# WS2812_hart.net
KiCad netlist of a schematic drawn in EAGLE
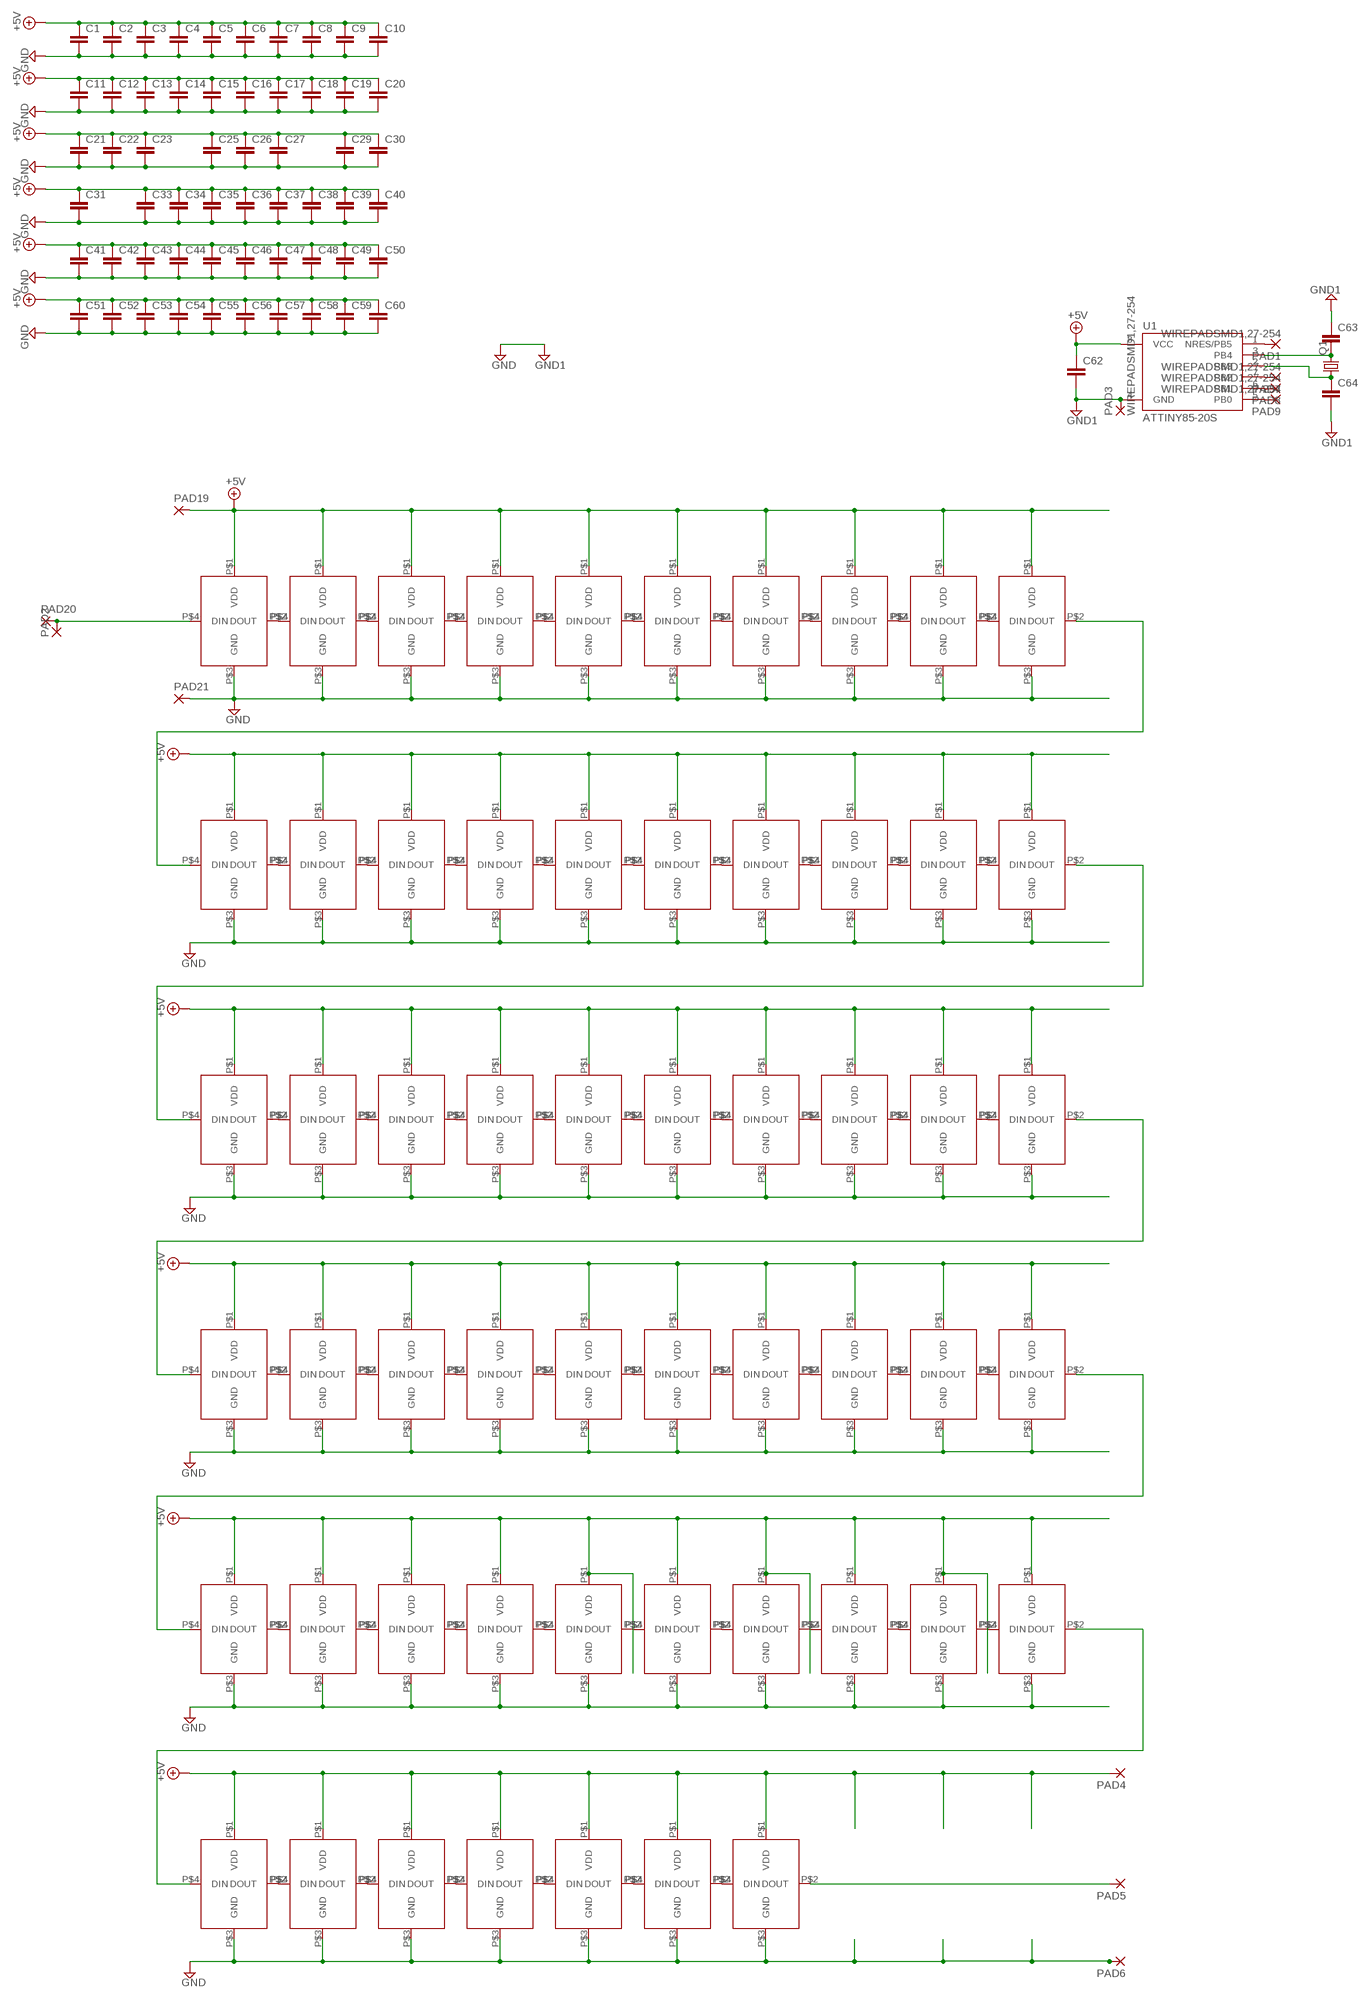
[diagram p0: schematic, sheet 1]

(export (version "E")
  (design (tool "Eeschema 10.0.6"))
  (components
    (comp (ref "C1")
      (value "C-EUC1206K")
      (footprint "eagle-import:C1206K")
      (libsource (lib "eagle-import") (part "C-EUC1206K"))
    )
    (comp (ref "C2")
      (value "C-EUC1206K")
      (footprint "eagle-import:C1206K")
      (libsource (lib "eagle-import") (part "C-EUC1206K"))
    )
    (comp (ref "C3")
      (value "C-EUC1206K")
      (footprint "eagle-import:C1206K")
      (libsource (lib "eagle-import") (part "C-EUC1206K"))
    )
    (comp (ref "C4")
      (value "C-EUC1206K")
      (footprint "eagle-import:C1206K")
      (libsource (lib "eagle-import") (part "C-EUC1206K"))
    )
    (comp (ref "C5")
      (value "C-EUC1206K")
      (footprint "eagle-import:C1206K")
      (libsource (lib "eagle-import") (part "C-EUC1206K"))
    )
    (comp (ref "C6")
      (value "C-EUC1206K")
      (footprint "eagle-import:C1206K")
      (libsource (lib "eagle-import") (part "C-EUC1206K"))
    )
    (comp (ref "C7")
      (value "C-EUC1206K")
      (footprint "eagle-import:C1206K")
      (libsource (lib "eagle-import") (part "C-EUC1206K"))
    )
    (comp (ref "C8")
      (value "C-EUC1206K")
      (footprint "eagle-import:C1206K")
      (libsource (lib "eagle-import") (part "C-EUC1206K"))
    )
    (comp (ref "C9")
      (value "C-EUC1206K")
      (footprint "eagle-import:C1206K")
      (libsource (lib "eagle-import") (part "C-EUC1206K"))
    )
    (comp (ref "C10")
      (value "C-EUC1206K")
      (footprint "eagle-import:C1206K")
      (libsource (lib "eagle-import") (part "C-EUC1206K"))
    )
    (comp (ref "C11")
      (value "C-EUC1206K")
      (footprint "eagle-import:C1206K")
      (libsource (lib "eagle-import") (part "C-EUC1206K"))
    )
    (comp (ref "C12")
      (value "C-EUC1206K")
      (footprint "eagle-import:C1206K")
      (libsource (lib "eagle-import") (part "C-EUC1206K"))
    )
    (comp (ref "C13")
      (value "C-EUC1206K")
      (footprint "eagle-import:C1206K")
      (libsource (lib "eagle-import") (part "C-EUC1206K"))
    )
    (comp (ref "C14")
      (value "C-EUC1206K")
      (footprint "eagle-import:C1206K")
      (libsource (lib "eagle-import") (part "C-EUC1206K"))
    )
    (comp (ref "C15")
      (value "C-EUC1206K")
      (footprint "eagle-import:C1206K")
      (libsource (lib "eagle-import") (part "C-EUC1206K"))
    )
    (comp (ref "C16")
      (value "C-EUC1206K")
      (footprint "eagle-import:C1206K")
      (libsource (lib "eagle-import") (part "C-EUC1206K"))
    )
    (comp (ref "C17")
      (value "C-EUC0805K")
      (footprint "eagle-import:C0805K")
      (libsource (lib "eagle-import") (part "C-EUC0805K"))
    )
    (comp (ref "C18")
      (value "C-EUC1206K")
      (footprint "eagle-import:C1206K")
      (libsource (lib "eagle-import") (part "C-EUC1206K"))
    )
    (comp (ref "C19")
      (value "C-EUC1206K")
      (footprint "eagle-import:C1206K")
      (libsource (lib "eagle-import") (part "C-EUC1206K"))
    )
    (comp (ref "C20")
      (value "C-EUC1206K")
      (footprint "eagle-import:C1206K")
      (libsource (lib "eagle-import") (part "C-EUC1206K"))
    )
    (comp (ref "C21")
      (value "C-EUC1206K")
      (footprint "eagle-import:C1206K")
      (libsource (lib "eagle-import") (part "C-EUC1206K"))
    )
    (comp (ref "C22")
      (value "C-EUC1206K")
      (footprint "eagle-import:C1206K")
      (libsource (lib "eagle-import") (part "C-EUC1206K"))
    )
    (comp (ref "C23")
      (value "C-EUC1206K")
      (footprint "eagle-import:C1206K")
      (libsource (lib "eagle-import") (part "C-EUC1206K"))
    )
    (comp (ref "C25")
      (value "C-EUC1206K")
      (footprint "eagle-import:C1206K")
      (libsource (lib "eagle-import") (part "C-EUC1206K"))
    )
    (comp (ref "C26")
      (value "C-EUC1206K")
      (footprint "eagle-import:C1206K")
      (libsource (lib "eagle-import") (part "C-EUC1206K"))
    )
    (comp (ref "C27")
      (value "C-EUC1206K")
      (footprint "eagle-import:C1206K")
      (libsource (lib "eagle-import") (part "C-EUC1206K"))
    )
    (comp (ref "C29")
      (value "C-EUC1206K")
      (footprint "eagle-import:C1206K")
      (libsource (lib "eagle-import") (part "C-EUC1206K"))
    )
    (comp (ref "C30")
      (value "C-EUC1206K")
      (footprint "eagle-import:C1206K")
      (libsource (lib "eagle-import") (part "C-EUC1206K"))
    )
    (comp (ref "C31")
      (value "C-EUC1206K")
      (footprint "eagle-import:C1206K")
      (libsource (lib "eagle-import") (part "C-EUC1206K"))
    )
    (comp (ref "C33")
      (value "C-EUC1206K")
      (footprint "eagle-import:C1206K")
      (libsource (lib "eagle-import") (part "C-EUC1206K"))
    )
    (comp (ref "C34")
      (value "C-EUC1206K")
      (footprint "eagle-import:C1206K")
      (libsource (lib "eagle-import") (part "C-EUC1206K"))
    )
    (comp (ref "C35")
      (value "C-EUC1206K")
      (footprint "eagle-import:C1206K")
      (libsource (lib "eagle-import") (part "C-EUC1206K"))
    )
    (comp (ref "C36")
      (value "C-EUC1206K")
      (footprint "eagle-import:C1206K")
      (libsource (lib "eagle-import") (part "C-EUC1206K"))
    )
    (comp (ref "C37")
      (value "C-EUC1206K")
      (footprint "eagle-import:C1206K")
      (libsource (lib "eagle-import") (part "C-EUC1206K"))
    )
    (comp (ref "C38")
      (value "C-EUC1206K")
      (footprint "eagle-import:C1206K")
      (libsource (lib "eagle-import") (part "C-EUC1206K"))
    )
    (comp (ref "C39")
      (value "C-EUC1206K")
      (footprint "eagle-import:C1206K")
      (libsource (lib "eagle-import") (part "C-EUC1206K"))
    )
    (comp (ref "C40")
      (value "C-EUC1206K")
      (footprint "eagle-import:C1206K")
      (libsource (lib "eagle-import") (part "C-EUC1206K"))
    )
    (comp (ref "C41")
      (value "C-EUC1206K")
      (footprint "eagle-import:C1206K")
      (libsource (lib "eagle-import") (part "C-EUC1206K"))
    )
    (comp (ref "C42")
      (value "C-EUC1206K")
      (footprint "eagle-import:C1206K")
      (libsource (lib "eagle-import") (part "C-EUC1206K"))
    )
    (comp (ref "C43")
      (value "C-EUC1206K")
      (footprint "eagle-import:C1206K")
      (libsource (lib "eagle-import") (part "C-EUC1206K"))
    )
    (comp (ref "C44")
      (value "C-EUC1206K")
      (footprint "eagle-import:C1206K")
      (libsource (lib "eagle-import") (part "C-EUC1206K"))
    )
    (comp (ref "C45")
      (value "C-EUC1206K")
      (footprint "eagle-import:C1206K")
      (libsource (lib "eagle-import") (part "C-EUC1206K"))
    )
    (comp (ref "C46")
      (value "C-EUC1206K")
      (footprint "eagle-import:C1206K")
      (libsource (lib "eagle-import") (part "C-EUC1206K"))
    )
    (comp (ref "C47")
      (value "C-EUC1206K")
      (footprint "eagle-import:C1206K")
      (libsource (lib "eagle-import") (part "C-EUC1206K"))
    )
    (comp (ref "C48")
      (value "C-EUC1206K")
      (footprint "eagle-import:C1206K")
      (libsource (lib "eagle-import") (part "C-EUC1206K"))
    )
    (comp (ref "C49")
      (value "C-EUC1206K")
      (footprint "eagle-import:C1206K")
      (libsource (lib "eagle-import") (part "C-EUC1206K"))
    )
    (comp (ref "C50")
      (value "C-EUC1206K")
      (footprint "eagle-import:C1206K")
      (libsource (lib "eagle-import") (part "C-EUC1206K"))
    )
    (comp (ref "C51")
      (value "C-EUC1206K")
      (footprint "eagle-import:C1206K")
      (libsource (lib "eagle-import") (part "C-EUC1206K"))
    )
    (comp (ref "C52")
      (value "C-EUC0805K")
      (footprint "eagle-import:C0805K")
      (libsource (lib "eagle-import") (part "C-EUC0805K"))
    )
    (comp (ref "C53")
      (value "C-EUC1206K")
      (footprint "eagle-import:C1206K")
      (libsource (lib "eagle-import") (part "C-EUC1206K"))
    )
    (comp (ref "C54")
      (value "C-EUC1206K")
      (footprint "eagle-import:C1206K")
      (libsource (lib "eagle-import") (part "C-EUC1206K"))
    )
    (comp (ref "C55")
      (value "C-EUC1206K")
      (footprint "eagle-import:C1206K")
      (libsource (lib "eagle-import") (part "C-EUC1206K"))
    )
    (comp (ref "C56")
      (value "C-EUC1206K")
      (footprint "eagle-import:C1206K")
      (libsource (lib "eagle-import") (part "C-EUC1206K"))
    )
    (comp (ref "C57")
      (value "C-EUC1206K")
      (footprint "eagle-import:C1206K")
      (libsource (lib "eagle-import") (part "C-EUC1206K"))
    )
    (comp (ref "C58")
      (value "C-EUC1206K")
      (footprint "eagle-import:C1206K")
      (libsource (lib "eagle-import") (part "C-EUC1206K"))
    )
    (comp (ref "C59")
      (value "C-EUC1206K")
      (footprint "eagle-import:C1206K")
      (libsource (lib "eagle-import") (part "C-EUC1206K"))
    )
    (comp (ref "C60")
      (value "C-EUC1206K")
      (footprint "eagle-import:C1206K")
      (libsource (lib "eagle-import") (part "C-EUC1206K"))
    )
    (comp (ref "C62")
      (value "C-EUC0805K")
      (footprint "eagle-import:C0805K")
      (libsource (lib "eagle-import") (part "C-EUC0805K"))
    )
    (comp (ref "C63")
      (value "C-EUC0603K")
      (footprint "eagle-import:C0603K")
      (libsource (lib "eagle-import") (part "C-EUC0603K"))
    )
    (comp (ref "C64")
      (value "C-EUC0603K")
      (footprint "eagle-import:C0603K")
      (libsource (lib "eagle-import") (part "C-EUC0603K"))
    )
    (comp (ref "PAD1")
      (value "WIREPADSMD1,27-254")
      (footprint "eagle-import:SMD1,27-2,54")
      (libsource (lib "eagle-import") (part "WIREPADSMD1,27-254"))
    )
    (comp (ref "PAD2")
      (value "SMD5")
      (footprint "eagle-import:SMD2,54-5,08")
      (libsource (lib "eagle-import") (part "SMD5"))
    )
    (comp (ref "PAD3")
      (value "WIREPADSMD1,27-254")
      (footprint "eagle-import:SMD1,27-2,54")
      (libsource (lib "eagle-import") (part "WIREPADSMD1,27-254"))
    )
    (comp (ref "PAD4")
      (value "1,6/0,8")
      (footprint "eagle-import:1,6_0,8")
      (libsource (lib "eagle-import") (part "1,6/0,8"))
    )
    (comp (ref "PAD5")
      (value "1,6/0,8")
      (footprint "eagle-import:1,6_0,8")
      (libsource (lib "eagle-import") (part "1,6/0,8"))
    )
    (comp (ref "PAD6")
      (value "1,6/0,8")
      (footprint "eagle-import:1,6_0,8")
      (libsource (lib "eagle-import") (part "1,6/0,8"))
    )
    (comp (ref "PAD7")
      (value "WIREPADSMD1,27-254")
      (footprint "eagle-import:SMD1,27-2,54")
      (libsource (lib "eagle-import") (part "WIREPADSMD1,27-254"))
    )
    (comp (ref "PAD8")
      (value "WIREPADSMD1,27-254")
      (footprint "eagle-import:SMD1,27-2,54")
      (libsource (lib "eagle-import") (part "WIREPADSMD1,27-254"))
    )
    (comp (ref "PAD9")
      (value "WIREPADSMD1,27-254")
      (footprint "eagle-import:SMD1,27-2,54")
      (libsource (lib "eagle-import") (part "WIREPADSMD1,27-254"))
    )
    (comp (ref "PAD19")
      (value "1,6/0,8")
      (footprint "eagle-import:1,6_0,8")
      (libsource (lib "eagle-import") (part "1,6/0,8"))
    )
    (comp (ref "PAD20")
      (value "1,6/0,8")
      (footprint "eagle-import:1,6_0,8")
      (libsource (lib "eagle-import") (part "1,6/0,8"))
    )
    (comp (ref "PAD21")
      (value "1,6/0,8")
      (footprint "eagle-import:1,6_0,8")
      (libsource (lib "eagle-import") (part "1,6/0,8"))
    )
    (comp (ref "Q1")
      (value "CRYSTALHC49S")
      (footprint "eagle-import:HC49_S")
      (libsource (lib "eagle-import") (part "CRYSTALHC49S"))
    )
    (comp (ref "U$1")
      (value "WS2812B")
      (footprint "eagle-import:PLCC-4")
      (libsource (lib "eagle-import") (part "WS2812B"))
    )
    (comp (ref "U$2")
      (value "WS2812B")
      (footprint "eagle-import:PLCC-4")
      (libsource (lib "eagle-import") (part "WS2812B"))
    )
    (comp (ref "U$3")
      (value "WS2812B")
      (footprint "eagle-import:PLCC-4")
      (libsource (lib "eagle-import") (part "WS2812B"))
    )
    (comp (ref "U$4")
      (value "WS2812B")
      (footprint "eagle-import:PLCC-4")
      (libsource (lib "eagle-import") (part "WS2812B"))
    )
    (comp (ref "U$5")
      (value "WS2812B")
      (footprint "eagle-import:PLCC-4")
      (libsource (lib "eagle-import") (part "WS2812B"))
    )
    (comp (ref "U$6")
      (value "WS2812B")
      (footprint "eagle-import:PLCC-4")
      (libsource (lib "eagle-import") (part "WS2812B"))
    )
    (comp (ref "U$7")
      (value "WS2812B")
      (footprint "eagle-import:PLCC-4")
      (libsource (lib "eagle-import") (part "WS2812B"))
    )
    (comp (ref "U$8")
      (value "WS2812B")
      (footprint "eagle-import:PLCC-4")
      (libsource (lib "eagle-import") (part "WS2812B"))
    )
    (comp (ref "U$9")
      (value "WS2812B")
      (footprint "eagle-import:PLCC-4")
      (libsource (lib "eagle-import") (part "WS2812B"))
    )
    (comp (ref "U$10")
      (value "WS2812B")
      (footprint "eagle-import:PLCC-4")
      (libsource (lib "eagle-import") (part "WS2812B"))
    )
    (comp (ref "U$11")
      (value "WS2812B")
      (footprint "eagle-import:PLCC-4")
      (libsource (lib "eagle-import") (part "WS2812B"))
    )
    (comp (ref "U$12")
      (value "WS2812B")
      (footprint "eagle-import:PLCC-4")
      (libsource (lib "eagle-import") (part "WS2812B"))
    )
    (comp (ref "U$13")
      (value "WS2812B")
      (footprint "eagle-import:PLCC-4")
      (libsource (lib "eagle-import") (part "WS2812B"))
    )
    (comp (ref "U$14")
      (value "WS2812B")
      (footprint "eagle-import:PLCC-4")
      (libsource (lib "eagle-import") (part "WS2812B"))
    )
    (comp (ref "U$15")
      (value "WS2812B")
      (footprint "eagle-import:PLCC-4")
      (libsource (lib "eagle-import") (part "WS2812B"))
    )
    (comp (ref "U$16")
      (value "WS2812B")
      (footprint "eagle-import:PLCC-4")
      (libsource (lib "eagle-import") (part "WS2812B"))
    )
    (comp (ref "U$17")
      (value "WS2812B")
      (footprint "eagle-import:PLCC-4")
      (libsource (lib "eagle-import") (part "WS2812B"))
    )
    (comp (ref "U$18")
      (value "WS2812B")
      (footprint "eagle-import:PLCC-4")
      (libsource (lib "eagle-import") (part "WS2812B"))
    )
    (comp (ref "U$19")
      (value "WS2812B")
      (footprint "eagle-import:PLCC-4")
      (libsource (lib "eagle-import") (part "WS2812B"))
    )
    (comp (ref "U$20")
      (value "WS2812B")
      (footprint "eagle-import:PLCC-4")
      (libsource (lib "eagle-import") (part "WS2812B"))
    )
    (comp (ref "U$21")
      (value "WS2812B")
      (footprint "eagle-import:PLCC-4")
      (libsource (lib "eagle-import") (part "WS2812B"))
    )
    (comp (ref "U$22")
      (value "WS2812B")
      (footprint "eagle-import:PLCC-4")
      (libsource (lib "eagle-import") (part "WS2812B"))
    )
    (comp (ref "U$23")
      (value "WS2812B")
      (footprint "eagle-import:PLCC-4")
      (libsource (lib "eagle-import") (part "WS2812B"))
    )
    (comp (ref "U$24")
      (value "WS2812B")
      (footprint "eagle-import:PLCC-4")
      (libsource (lib "eagle-import") (part "WS2812B"))
    )
    (comp (ref "U$25")
      (value "WS2812B")
      (footprint "eagle-import:PLCC-4")
      (libsource (lib "eagle-import") (part "WS2812B"))
    )
    (comp (ref "U$26")
      (value "WS2812B")
      (footprint "eagle-import:PLCC-4")
      (libsource (lib "eagle-import") (part "WS2812B"))
    )
    (comp (ref "U$27")
      (value "WS2812B")
      (footprint "eagle-import:PLCC-4")
      (libsource (lib "eagle-import") (part "WS2812B"))
    )
    (comp (ref "U$28")
      (value "WS2812B")
      (footprint "eagle-import:PLCC-4")
      (libsource (lib "eagle-import") (part "WS2812B"))
    )
    (comp (ref "U$29")
      (value "WS2812B")
      (footprint "eagle-import:PLCC-4")
      (libsource (lib "eagle-import") (part "WS2812B"))
    )
    (comp (ref "U$30")
      (value "WS2812B")
      (footprint "eagle-import:PLCC-4")
      (libsource (lib "eagle-import") (part "WS2812B"))
    )
    (comp (ref "U$31")
      (value "WS2812B")
      (footprint "eagle-import:PLCC-4")
      (libsource (lib "eagle-import") (part "WS2812B"))
    )
    (comp (ref "U$32")
      (value "WS2812B")
      (footprint "eagle-import:PLCC-4")
      (libsource (lib "eagle-import") (part "WS2812B"))
    )
    (comp (ref "U$33")
      (value "WS2812B")
      (footprint "eagle-import:PLCC-4")
      (libsource (lib "eagle-import") (part "WS2812B"))
    )
    (comp (ref "U$34")
      (value "WS2812B")
      (footprint "eagle-import:PLCC-4")
      (libsource (lib "eagle-import") (part "WS2812B"))
    )
    (comp (ref "U$35")
      (value "WS2812B")
      (footprint "eagle-import:PLCC-4")
      (libsource (lib "eagle-import") (part "WS2812B"))
    )
    (comp (ref "U$36")
      (value "WS2812B")
      (footprint "eagle-import:PLCC-4")
      (libsource (lib "eagle-import") (part "WS2812B"))
    )
    (comp (ref "U$37")
      (value "WS2812B")
      (footprint "eagle-import:PLCC-4")
      (libsource (lib "eagle-import") (part "WS2812B"))
    )
    (comp (ref "U$38")
      (value "WS2812B")
      (footprint "eagle-import:PLCC-4")
      (libsource (lib "eagle-import") (part "WS2812B"))
    )
    (comp (ref "U$39")
      (value "WS2812B")
      (footprint "eagle-import:PLCC-4")
      (libsource (lib "eagle-import") (part "WS2812B"))
    )
    (comp (ref "U$40")
      (value "WS2812B")
      (footprint "eagle-import:PLCC-4")
      (libsource (lib "eagle-import") (part "WS2812B"))
    )
    (comp (ref "U$41")
      (value "WS2812B")
      (footprint "eagle-import:PLCC-4")
      (libsource (lib "eagle-import") (part "WS2812B"))
    )
    (comp (ref "U$42")
      (value "WS2812B")
      (footprint "eagle-import:PLCC-4")
      (libsource (lib "eagle-import") (part "WS2812B"))
    )
    (comp (ref "U$43")
      (value "WS2812B")
      (footprint "eagle-import:PLCC-4")
      (libsource (lib "eagle-import") (part "WS2812B"))
    )
    (comp (ref "U$44")
      (value "WS2812B")
      (footprint "eagle-import:PLCC-4")
      (libsource (lib "eagle-import") (part "WS2812B"))
    )
    (comp (ref "U$45")
      (value "WS2812B")
      (footprint "eagle-import:PLCC-4")
      (libsource (lib "eagle-import") (part "WS2812B"))
    )
    (comp (ref "U$46")
      (value "WS2812B")
      (footprint "eagle-import:PLCC-4")
      (libsource (lib "eagle-import") (part "WS2812B"))
    )
    (comp (ref "U$47")
      (value "WS2812B")
      (footprint "eagle-import:PLCC-4")
      (libsource (lib "eagle-import") (part "WS2812B"))
    )
    (comp (ref "U$48")
      (value "WS2812B")
      (footprint "eagle-import:PLCC-4")
      (libsource (lib "eagle-import") (part "WS2812B"))
    )
    (comp (ref "U$49")
      (value "WS2812B")
      (footprint "eagle-import:PLCC-4")
      (libsource (lib "eagle-import") (part "WS2812B"))
    )
    (comp (ref "U$50")
      (value "WS2812B")
      (footprint "eagle-import:PLCC-4")
      (libsource (lib "eagle-import") (part "WS2812B"))
    )
    (comp (ref "U$51")
      (value "WS2812B")
      (footprint "eagle-import:PLCC-4")
      (libsource (lib "eagle-import") (part "WS2812B"))
    )
    (comp (ref "U$52")
      (value "WS2812B")
      (footprint "eagle-import:PLCC-4")
      (libsource (lib "eagle-import") (part "WS2812B"))
    )
    (comp (ref "U$53")
      (value "WS2812B")
      (footprint "eagle-import:PLCC-4")
      (libsource (lib "eagle-import") (part "WS2812B"))
    )
    (comp (ref "U$54")
      (value "WS2812B")
      (footprint "eagle-import:PLCC-4")
      (libsource (lib "eagle-import") (part "WS2812B"))
    )
    (comp (ref "U$55")
      (value "WS2812B")
      (footprint "eagle-import:PLCC-4")
      (libsource (lib "eagle-import") (part "WS2812B"))
    )
    (comp (ref "U$56")
      (value "WS2812B")
      (footprint "eagle-import:PLCC-4")
      (libsource (lib "eagle-import") (part "WS2812B"))
    )
    (comp (ref "U$57")
      (value "WS2812B")
      (footprint "eagle-import:PLCC-4")
      (libsource (lib "eagle-import") (part "WS2812B"))
    )
    (comp (ref "U1")
      (value "ATTINY85-20S")
      (footprint "eagle-import:SOIC8_EIAJ_208MIL")
      (libsource (lib "eagle-import") (part "ATTINY85S-20"))
    )
  )
  (nets
    (net (code "1") (name "+5V") (class "Default")
      (node (ref "C1") (pin "1") (pinfunction "1_1") (pintype "passive"))
      (node (ref "C10") (pin "1") (pinfunction "1_1") (pintype "passive"))
      (node (ref "C11") (pin "1") (pinfunction "1_1") (pintype "passive"))
      (node (ref "C12") (pin "1") (pinfunction "1_1") (pintype "passive"))
      (node (ref "C13") (pin "1") (pinfunction "1_1") (pintype "passive"))
      (node (ref "C14") (pin "1") (pinfunction "1_1") (pintype "passive"))
      (node (ref "C15") (pin "1") (pinfunction "1_1") (pintype "passive"))
      (node (ref "C16") (pin "1") (pinfunction "1_1") (pintype "passive"))
      (node (ref "C17") (pin "1") (pinfunction "1_1") (pintype "passive"))
      (node (ref "C18") (pin "1") (pinfunction "1_1") (pintype "passive"))
      (node (ref "C19") (pin "1") (pinfunction "1_1") (pintype "passive"))
      (node (ref "C2") (pin "1") (pinfunction "1_1") (pintype "passive"))
      (node (ref "C20") (pin "1") (pinfunction "1_1") (pintype "passive"))
      (node (ref "C21") (pin "1") (pinfunction "1_1") (pintype "passive"))
      (node (ref "C22") (pin "1") (pinfunction "1_1") (pintype "passive"))
      (node (ref "C23") (pin "1") (pinfunction "1_1") (pintype "passive"))
      (node (ref "C25") (pin "1") (pinfunction "1_1") (pintype "passive"))
      (node (ref "C26") (pin "1") (pinfunction "1_1") (pintype "passive"))
      (node (ref "C27") (pin "1") (pinfunction "1_1") (pintype "passive"))
      (node (ref "C29") (pin "1") (pinfunction "1_1") (pintype "passive"))
      (node (ref "C3") (pin "1") (pinfunction "1_1") (pintype "passive"))
      (node (ref "C30") (pin "1") (pinfunction "1_1") (pintype "passive"))
      (node (ref "C31") (pin "1") (pinfunction "1_1") (pintype "passive"))
      (node (ref "C33") (pin "1") (pinfunction "1_1") (pintype "passive"))
      (node (ref "C34") (pin "1") (pinfunction "1_1") (pintype "passive"))
      (node (ref "C35") (pin "1") (pinfunction "1_1") (pintype "passive"))
      (node (ref "C36") (pin "1") (pinfunction "1_1") (pintype "passive"))
      (node (ref "C37") (pin "1") (pinfunction "1_1") (pintype "passive"))
      (node (ref "C38") (pin "1") (pinfunction "1_1") (pintype "passive"))
      (node (ref "C39") (pin "1") (pinfunction "1_1") (pintype "passive"))
      (node (ref "C4") (pin "1") (pinfunction "1_1") (pintype "passive"))
      (node (ref "C40") (pin "1") (pinfunction "1_1") (pintype "passive"))
      (node (ref "C41") (pin "1") (pinfunction "1_1") (pintype "passive"))
      (node (ref "C42") (pin "1") (pinfunction "1_1") (pintype "passive"))
      (node (ref "C43") (pin "1") (pinfunction "1_1") (pintype "passive"))
      (node (ref "C44") (pin "1") (pinfunction "1_1") (pintype "passive"))
      (node (ref "C45") (pin "1") (pinfunction "1_1") (pintype "passive"))
      (node (ref "C46") (pin "1") (pinfunction "1_1") (pintype "passive"))
      (node (ref "C47") (pin "1") (pinfunction "1_1") (pintype "passive"))
      (node (ref "C48") (pin "1") (pinfunction "1_1") (pintype "passive"))
      (node (ref "C49") (pin "1") (pinfunction "1_1") (pintype "passive"))
      (node (ref "C5") (pin "1") (pinfunction "1_1") (pintype "passive"))
      (node (ref "C50") (pin "1") (pinfunction "1_1") (pintype "passive"))
      (node (ref "C51") (pin "1") (pinfunction "1_1") (pintype "passive"))
      (node (ref "C52") (pin "1") (pinfunction "1_1") (pintype "passive"))
      (node (ref "C53") (pin "1") (pinfunction "1_1") (pintype "passive"))
      (node (ref "C54") (pin "1") (pinfunction "1_1") (pintype "passive"))
      (node (ref "C55") (pin "1") (pinfunction "1_1") (pintype "passive"))
      (node (ref "C56") (pin "1") (pinfunction "1_1") (pintype "passive"))
      (node (ref "C57") (pin "1") (pinfunction "1_1") (pintype "passive"))
      (node (ref "C58") (pin "1") (pinfunction "1_1") (pintype "passive"))
      (node (ref "C59") (pin "1") (pinfunction "1_1") (pintype "passive"))
      (node (ref "C6") (pin "1") (pinfunction "1_1") (pintype "passive"))
      (node (ref "C60") (pin "1") (pinfunction "1_1") (pintype "passive"))
      (node (ref "C62") (pin "1") (pinfunction "1_1") (pintype "passive"))
      (node (ref "C7") (pin "1") (pinfunction "1_1") (pintype "passive"))
      (node (ref "C8") (pin "1") (pinfunction "1_1") (pintype "passive"))
      (node (ref "C9") (pin "1") (pinfunction "1_1") (pintype "passive"))
      (node (ref "PAD19") (pin "1") (pinfunction "P_1") (pintype "passive"))
      (node (ref "PAD4") (pin "1") (pinfunction "P_1") (pintype "passive"))
      (node (ref "U$1") (pin "P$1") (pinfunction "VDD_P$1") (pintype "power_in"))
      (node (ref "U$10") (pin "P$1") (pinfunction "VDD_P$1") (pintype "power_in"))
      (node (ref "U$11") (pin "P$1") (pinfunction "VDD_P$1") (pintype "power_in"))
      (node (ref "U$12") (pin "P$1") (pinfunction "VDD_P$1") (pintype "power_in"))
      (node (ref "U$13") (pin "P$1") (pinfunction "VDD_P$1") (pintype "power_in"))
      (node (ref "U$14") (pin "P$1") (pinfunction "VDD_P$1") (pintype "power_in"))
      (node (ref "U$15") (pin "P$1") (pinfunction "VDD_P$1") (pintype "power_in"))
      (node (ref "U$16") (pin "P$1") (pinfunction "VDD_P$1") (pintype "power_in"))
      (node (ref "U$17") (pin "P$1") (pinfunction "VDD_P$1") (pintype "power_in"))
      (node (ref "U$18") (pin "P$1") (pinfunction "VDD_P$1") (pintype "power_in"))
      (node (ref "U$19") (pin "P$1") (pinfunction "VDD_P$1") (pintype "power_in"))
      (node (ref "U$2") (pin "P$1") (pinfunction "VDD_P$1") (pintype "power_in"))
      (node (ref "U$20") (pin "P$1") (pinfunction "VDD_P$1") (pintype "power_in"))
      (node (ref "U$21") (pin "P$1") (pinfunction "VDD_P$1") (pintype "power_in"))
      (node (ref "U$22") (pin "P$1") (pinfunction "VDD_P$1") (pintype "power_in"))
      (node (ref "U$23") (pin "P$1") (pinfunction "VDD_P$1") (pintype "power_in"))
      (node (ref "U$24") (pin "P$1") (pinfunction "VDD_P$1") (pintype "power_in"))
      (node (ref "U$25") (pin "P$1") (pinfunction "VDD_P$1") (pintype "power_in"))
      (node (ref "U$26") (pin "P$1") (pinfunction "VDD_P$1") (pintype "power_in"))
      (node (ref "U$27") (pin "P$1") (pinfunction "VDD_P$1") (pintype "power_in"))
      (node (ref "U$28") (pin "P$1") (pinfunction "VDD_P$1") (pintype "power_in"))
      (node (ref "U$29") (pin "P$1") (pinfunction "VDD_P$1") (pintype "power_in"))
      (node (ref "U$3") (pin "P$1") (pinfunction "VDD_P$1") (pintype "power_in"))
      (node (ref "U$30") (pin "P$1") (pinfunction "VDD_P$1") (pintype "power_in"))
      (node (ref "U$31") (pin "P$1") (pinfunction "VDD_P$1") (pintype "power_in"))
      (node (ref "U$32") (pin "P$1") (pinfunction "VDD_P$1") (pintype "power_in"))
      (node (ref "U$33") (pin "P$1") (pinfunction "VDD_P$1") (pintype "power_in"))
      (node (ref "U$34") (pin "P$1") (pinfunction "VDD_P$1") (pintype "power_in"))
      (node (ref "U$35") (pin "P$1") (pinfunction "VDD_P$1") (pintype "power_in"))
      (node (ref "U$36") (pin "P$1") (pinfunction "VDD_P$1") (pintype "power_in"))
      (node (ref "U$37") (pin "P$1") (pinfunction "VDD_P$1") (pintype "power_in"))
      (node (ref "U$38") (pin "P$1") (pinfunction "VDD_P$1") (pintype "power_in"))
      (node (ref "U$39") (pin "P$1") (pinfunction "VDD_P$1") (pintype "power_in"))
      (node (ref "U$4") (pin "P$1") (pinfunction "VDD_P$1") (pintype "power_in"))
      (node (ref "U$40") (pin "P$1") (pinfunction "VDD_P$1") (pintype "power_in"))
      (node (ref "U$41") (pin "P$1") (pinfunction "VDD_P$1") (pintype "power_in"))
      (node (ref "U$42") (pin "P$1") (pinfunction "VDD_P$1") (pintype "power_in"))
      (node (ref "U$43") (pin "P$1") (pinfunction "VDD_P$1") (pintype "power_in"))
      (node (ref "U$44") (pin "P$1") (pinfunction "VDD_P$1") (pintype "power_in"))
      (node (ref "U$45") (pin "P$1") (pinfunction "VDD_P$1") (pintype "power_in"))
      (node (ref "U$46") (pin "P$1") (pinfunction "VDD_P$1") (pintype "power_in"))
      (node (ref "U$47") (pin "P$1") (pinfunction "VDD_P$1") (pintype "power_in"))
      (node (ref "U$48") (pin "P$1") (pinfunction "VDD_P$1") (pintype "power_in"))
      (node (ref "U$49") (pin "P$1") (pinfunction "VDD_P$1") (pintype "power_in"))
      (node (ref "U$5") (pin "P$1") (pinfunction "VDD_P$1") (pintype "power_in"))
      (node (ref "U$50") (pin "P$1") (pinfunction "VDD_P$1") (pintype "power_in"))
      (node (ref "U$51") (pin "P$1") (pinfunction "VDD_P$1") (pintype "power_in"))
      (node (ref "U$52") (pin "P$1") (pinfunction "VDD_P$1") (pintype "power_in"))
      (node (ref "U$53") (pin "P$1") (pinfunction "VDD_P$1") (pintype "power_in"))
      (node (ref "U$54") (pin "P$1") (pinfunction "VDD_P$1") (pintype "power_in"))
      (node (ref "U$55") (pin "P$1") (pinfunction "VDD_P$1") (pintype "power_in"))
      (node (ref "U$56") (pin "P$1") (pinfunction "VDD_P$1") (pintype "power_in"))
      (node (ref "U$57") (pin "P$1") (pinfunction "VDD_P$1") (pintype "power_in"))
      (node (ref "U$6") (pin "P$1") (pinfunction "VDD_P$1") (pintype "power_in"))
      (node (ref "U$7") (pin "P$1") (pinfunction "VDD_P$1") (pintype "power_in"))
      (node (ref "U$8") (pin "P$1") (pinfunction "VDD_P$1") (pintype "power_in"))
      (node (ref "U$9") (pin "P$1") (pinfunction "VDD_P$1") (pintype "power_in"))
      (node (ref "U1") (pin "8") (pinfunction "VCC_8") (pintype "power_in"))
    )
    (net (code "2") (name "GND") (class "Default")
      (node (ref "C1") (pin "2") (pinfunction "2_2") (pintype "passive"))
      (node (ref "C10") (pin "2") (pinfunction "2_2") (pintype "passive"))
      (node (ref "C11") (pin "2") (pinfunction "2_2") (pintype "passive"))
      (node (ref "C12") (pin "2") (pinfunction "2_2") (pintype "passive"))
      (node (ref "C13") (pin "2") (pinfunction "2_2") (pintype "passive"))
      (node (ref "C14") (pin "2") (pinfunction "2_2") (pintype "passive"))
      (node (ref "C15") (pin "2") (pinfunction "2_2") (pintype "passive"))
      (node (ref "C16") (pin "2") (pinfunction "2_2") (pintype "passive"))
      (node (ref "C17") (pin "2") (pinfunction "2_2") (pintype "passive"))
      (node (ref "C18") (pin "2") (pinfunction "2_2") (pintype "passive"))
      (node (ref "C19") (pin "2") (pinfunction "2_2") (pintype "passive"))
      (node (ref "C2") (pin "2") (pinfunction "2_2") (pintype "passive"))
      (node (ref "C20") (pin "2") (pinfunction "2_2") (pintype "passive"))
      (node (ref "C21") (pin "2") (pinfunction "2_2") (pintype "passive"))
      (node (ref "C22") (pin "2") (pinfunction "2_2") (pintype "passive"))
      (node (ref "C23") (pin "2") (pinfunction "2_2") (pintype "passive"))
      (node (ref "C25") (pin "2") (pinfunction "2_2") (pintype "passive"))
      (node (ref "C26") (pin "2") (pinfunction "2_2") (pintype "passive"))
      (node (ref "C27") (pin "2") (pinfunction "2_2") (pintype "passive"))
      (node (ref "C29") (pin "2") (pinfunction "2_2") (pintype "passive"))
      (node (ref "C3") (pin "2") (pinfunction "2_2") (pintype "passive"))
      (node (ref "C30") (pin "2") (pinfunction "2_2") (pintype "passive"))
      (node (ref "C31") (pin "2") (pinfunction "2_2") (pintype "passive"))
      (node (ref "C33") (pin "2") (pinfunction "2_2") (pintype "passive"))
      (node (ref "C34") (pin "2") (pinfunction "2_2") (pintype "passive"))
      (node (ref "C35") (pin "2") (pinfunction "2_2") (pintype "passive"))
      (node (ref "C36") (pin "2") (pinfunction "2_2") (pintype "passive"))
      (node (ref "C37") (pin "2") (pinfunction "2_2") (pintype "passive"))
      (node (ref "C38") (pin "2") (pinfunction "2_2") (pintype "passive"))
      (node (ref "C39") (pin "2") (pinfunction "2_2") (pintype "passive"))
      (node (ref "C4") (pin "2") (pinfunction "2_2") (pintype "passive"))
      (node (ref "C40") (pin "2") (pinfunction "2_2") (pintype "passive"))
      (node (ref "C41") (pin "2") (pinfunction "2_2") (pintype "passive"))
      (node (ref "C42") (pin "2") (pinfunction "2_2") (pintype "passive"))
      (node (ref "C43") (pin "2") (pinfunction "2_2") (pintype "passive"))
      (node (ref "C44") (pin "2") (pinfunction "2_2") (pintype "passive"))
      (node (ref "C45") (pin "2") (pinfunction "2_2") (pintype "passive"))
      (node (ref "C46") (pin "2") (pinfunction "2_2") (pintype "passive"))
      (node (ref "C47") (pin "2") (pinfunction "2_2") (pintype "passive"))
      (node (ref "C48") (pin "2") (pinfunction "2_2") (pintype "passive"))
      (node (ref "C49") (pin "2") (pinfunction "2_2") (pintype "passive"))
      (node (ref "C5") (pin "2") (pinfunction "2_2") (pintype "passive"))
      (node (ref "C50") (pin "2") (pinfunction "2_2") (pintype "passive"))
      (node (ref "C51") (pin "2") (pinfunction "2_2") (pintype "passive"))
      (node (ref "C52") (pin "2") (pinfunction "2_2") (pintype "passive"))
      (node (ref "C53") (pin "2") (pinfunction "2_2") (pintype "passive"))
      (node (ref "C54") (pin "2") (pinfunction "2_2") (pintype "passive"))
      (node (ref "C55") (pin "2") (pinfunction "2_2") (pintype "passive"))
      (node (ref "C56") (pin "2") (pinfunction "2_2") (pintype "passive"))
      (node (ref "C57") (pin "2") (pinfunction "2_2") (pintype "passive"))
      (node (ref "C58") (pin "2") (pinfunction "2_2") (pintype "passive"))
      (node (ref "C59") (pin "2") (pinfunction "2_2") (pintype "passive"))
      (node (ref "C6") (pin "2") (pinfunction "2_2") (pintype "passive"))
      (node (ref "C60") (pin "2") (pinfunction "2_2") (pintype "passive"))
      (node (ref "C62") (pin "2") (pinfunction "2_2") (pintype "passive"))
      (node (ref "C63") (pin "1") (pinfunction "1_1") (pintype "passive"))
      (node (ref "C64") (pin "2") (pinfunction "2_2") (pintype "passive"))
      (node (ref "C7") (pin "2") (pinfunction "2_2") (pintype "passive"))
      (node (ref "C8") (pin "2") (pinfunction "2_2") (pintype "passive"))
      (node (ref "C9") (pin "2") (pinfunction "2_2") (pintype "passive"))
      (node (ref "PAD21") (pin "1") (pinfunction "P_1") (pintype "passive"))
      (node (ref "PAD3") (pin "1") (pinfunction "P_1") (pintype "passive"))
      (node (ref "PAD6") (pin "1") (pinfunction "P_1") (pintype "passive"))
      (node (ref "U$1") (pin "P$3") (pinfunction "GND_P$3") (pintype "power_in"))
      (node (ref "U$10") (pin "P$3") (pinfunction "GND_P$3") (pintype "power_in"))
      (node (ref "U$11") (pin "P$3") (pinfunction "GND_P$3") (pintype "power_in"))
      (node (ref "U$12") (pin "P$3") (pinfunction "GND_P$3") (pintype "power_in"))
      (node (ref "U$13") (pin "P$3") (pinfunction "GND_P$3") (pintype "power_in"))
      (node (ref "U$14") (pin "P$3") (pinfunction "GND_P$3") (pintype "power_in"))
      (node (ref "U$15") (pin "P$3") (pinfunction "GND_P$3") (pintype "power_in"))
      (node (ref "U$16") (pin "P$3") (pinfunction "GND_P$3") (pintype "power_in"))
      (node (ref "U$17") (pin "P$3") (pinfunction "GND_P$3") (pintype "power_in"))
      (node (ref "U$18") (pin "P$3") (pinfunction "GND_P$3") (pintype "power_in"))
      (node (ref "U$19") (pin "P$3") (pinfunction "GND_P$3") (pintype "power_in"))
      (node (ref "U$2") (pin "P$3") (pinfunction "GND_P$3") (pintype "power_in"))
      (node (ref "U$20") (pin "P$3") (pinfunction "GND_P$3") (pintype "power_in"))
      (node (ref "U$21") (pin "P$3") (pinfunction "GND_P$3") (pintype "power_in"))
      (node (ref "U$22") (pin "P$3") (pinfunction "GND_P$3") (pintype "power_in"))
      (node (ref "U$23") (pin "P$3") (pinfunction "GND_P$3") (pintype "power_in"))
      (node (ref "U$24") (pin "P$3") (pinfunction "GND_P$3") (pintype "power_in"))
      (node (ref "U$25") (pin "P$3") (pinfunction "GND_P$3") (pintype "power_in"))
      (node (ref "U$26") (pin "P$3") (pinfunction "GND_P$3") (pintype "power_in"))
      (node (ref "U$27") (pin "P$3") (pinfunction "GND_P$3") (pintype "power_in"))
      (node (ref "U$28") (pin "P$3") (pinfunction "GND_P$3") (pintype "power_in"))
      (node (ref "U$29") (pin "P$3") (pinfunction "GND_P$3") (pintype "power_in"))
      (node (ref "U$3") (pin "P$3") (pinfunction "GND_P$3") (pintype "power_in"))
      (node (ref "U$30") (pin "P$3") (pinfunction "GND_P$3") (pintype "power_in"))
      (node (ref "U$31") (pin "P$3") (pinfunction "GND_P$3") (pintype "power_in"))
      (node (ref "U$32") (pin "P$3") (pinfunction "GND_P$3") (pintype "power_in"))
      (node (ref "U$33") (pin "P$3") (pinfunction "GND_P$3") (pintype "power_in"))
      (node (ref "U$34") (pin "P$3") (pinfunction "GND_P$3") (pintype "power_in"))
      (node (ref "U$35") (pin "P$3") (pinfunction "GND_P$3") (pintype "power_in"))
      (node (ref "U$36") (pin "P$3") (pinfunction "GND_P$3") (pintype "power_in"))
      (node (ref "U$37") (pin "P$3") (pinfunction "GND_P$3") (pintype "power_in"))
      (node (ref "U$38") (pin "P$3") (pinfunction "GND_P$3") (pintype "power_in"))
      (node (ref "U$39") (pin "P$3") (pinfunction "GND_P$3") (pintype "power_in"))
      (node (ref "U$4") (pin "P$3") (pinfunction "GND_P$3") (pintype "power_in"))
      (node (ref "U$40") (pin "P$3") (pinfunction "GND_P$3") (pintype "power_in"))
      (node (ref "U$41") (pin "P$3") (pinfunction "GND_P$3") (pintype "power_in"))
      (node (ref "U$42") (pin "P$3") (pinfunction "GND_P$3") (pintype "power_in"))
      (node (ref "U$43") (pin "P$3") (pinfunction "GND_P$3") (pintype "power_in"))
      (node (ref "U$44") (pin "P$3") (pinfunction "GND_P$3") (pintype "power_in"))
      (node (ref "U$45") (pin "P$3") (pinfunction "GND_P$3") (pintype "power_in"))
      (node (ref "U$46") (pin "P$3") (pinfunction "GND_P$3") (pintype "power_in"))
      (node (ref "U$47") (pin "P$3") (pinfunction "GND_P$3") (pintype "power_in"))
      (node (ref "U$48") (pin "P$3") (pinfunction "GND_P$3") (pintype "power_in"))
      (node (ref "U$49") (pin "P$3") (pinfunction "GND_P$3") (pintype "power_in"))
      (node (ref "U$5") (pin "P$3") (pinfunction "GND_P$3") (pintype "power_in"))
      (node (ref "U$50") (pin "P$3") (pinfunction "GND_P$3") (pintype "power_in"))
      (node (ref "U$51") (pin "P$3") (pinfunction "GND_P$3") (pintype "power_in"))
      (node (ref "U$52") (pin "P$3") (pinfunction "GND_P$3") (pintype "power_in"))
      (node (ref "U$53") (pin "P$3") (pinfunction "GND_P$3") (pintype "power_in"))
      (node (ref "U$54") (pin "P$3") (pinfunction "GND_P$3") (pintype "power_in"))
      (node (ref "U$55") (pin "P$3") (pinfunction "GND_P$3") (pintype "power_in"))
      (node (ref "U$56") (pin "P$3") (pinfunction "GND_P$3") (pintype "power_in"))
      (node (ref "U$57") (pin "P$3") (pinfunction "GND_P$3") (pintype "power_in"))
      (node (ref "U$6") (pin "P$3") (pinfunction "GND_P$3") (pintype "power_in"))
      (node (ref "U$7") (pin "P$3") (pinfunction "GND_P$3") (pintype "power_in"))
      (node (ref "U$8") (pin "P$3") (pinfunction "GND_P$3") (pintype "power_in"))
      (node (ref "U$9") (pin "P$3") (pinfunction "GND_P$3") (pintype "power_in"))
      (node (ref "U1") (pin "4") (pinfunction "GND_4") (pintype "power_in"))
    )
    (net (code "3") (name "Net-(PAD1-P)") (class "Default")
      (node (ref "PAD1") (pin "1") (pinfunction "P_1") (pintype "passive"))
      (node (ref "U1") (pin "1") (pinfunction "NRES/PB5_1") (pintype "bidirectional"))
    )
    (net (code "4") (name "Net-(PAD2-P)") (class "Default")
      (node (ref "PAD2") (pin "1") (pinfunction "P_1") (pintype "passive"))
      (node (ref "PAD20") (pin "1") (pinfunction "P_1") (pintype "passive"))
      (node (ref "U$31") (pin "P$4") (pinfunction "DIN_P$4") (pintype "input"))
    )
    (net (code "5") (name "Net-(PAD5-P)") (class "Default")
      (node (ref "PAD5") (pin "1") (pinfunction "P_1") (pintype "passive"))
      (node (ref "U$57") (pin "P$2") (pinfunction "DOUT_P$2") (pintype "output"))
    )
    (net (code "6") (name "Net-(PAD7-P)") (class "Default")
      (node (ref "PAD7") (pin "1") (pinfunction "P_1") (pintype "passive"))
      (node (ref "U1") (pin "7") (pinfunction "PB2_7") (pintype "bidirectional"))
    )
    (net (code "7") (name "Net-(PAD8-P)") (class "Default")
      (node (ref "PAD8") (pin "1") (pinfunction "P_1") (pintype "passive"))
      (node (ref "U1") (pin "6") (pinfunction "PB1_6") (pintype "bidirectional"))
    )
    (net (code "8") (name "Net-(PAD9-P)") (class "Default")
      (node (ref "PAD9") (pin "1") (pinfunction "P_1") (pintype "passive"))
      (node (ref "U1") (pin "5") (pinfunction "PB0_5") (pintype "bidirectional"))
    )
    (net (code "9") (name "Net-(U$1-DIN)") (class "Default")
      (node (ref "U$1") (pin "P$4") (pinfunction "DIN_P$4") (pintype "input"))
      (node (ref "U$10") (pin "P$2") (pinfunction "DOUT_P$2") (pintype "output"))
    )
    (net (code "10") (name "Net-(U$1-DOUT)") (class "Default")
      (node (ref "U$1") (pin "P$2") (pinfunction "DOUT_P$2") (pintype "output"))
      (node (ref "U$41") (pin "P$4") (pinfunction "DIN_P$4") (pintype "input"))
    )
    (net (code "11") (name "Net-(U$2-DIN)") (class "Default")
      (node (ref "U$2") (pin "P$4") (pinfunction "DIN_P$4") (pintype "input"))
      (node (ref "U$20") (pin "P$2") (pinfunction "DOUT_P$2") (pintype "output"))
    )
    (net (code "12") (name "Net-(U$2-DOUT)") (class "Default")
      (node (ref "U$2") (pin "P$2") (pinfunction "DOUT_P$2") (pintype "output"))
      (node (ref "U$3") (pin "P$4") (pinfunction "DIN_P$4") (pintype "input"))
    )
    (net (code "13") (name "Net-(U$3-DOUT)") (class "Default")
      (node (ref "U$3") (pin "P$2") (pinfunction "DOUT_P$2") (pintype "output"))
      (node (ref "U$4") (pin "P$4") (pinfunction "DIN_P$4") (pintype "input"))
    )
    (net (code "14") (name "Net-(U$4-DOUT)") (class "Default")
      (node (ref "U$4") (pin "P$2") (pinfunction "DOUT_P$2") (pintype "output"))
      (node (ref "U$5") (pin "P$4") (pinfunction "DIN_P$4") (pintype "input"))
    )
    (net (code "15") (name "Net-(U$5-DOUT)") (class "Default")
      (node (ref "U$5") (pin "P$2") (pinfunction "DOUT_P$2") (pintype "output"))
      (node (ref "U$6") (pin "P$4") (pinfunction "DIN_P$4") (pintype "input"))
    )
    (net (code "16") (name "Net-(U$6-DOUT)") (class "Default")
      (node (ref "U$6") (pin "P$2") (pinfunction "DOUT_P$2") (pintype "output"))
      (node (ref "U$7") (pin "P$4") (pinfunction "DIN_P$4") (pintype "input"))
    )
    (net (code "17") (name "Net-(U$7-DOUT)") (class "Default")
      (node (ref "U$7") (pin "P$2") (pinfunction "DOUT_P$2") (pintype "output"))
      (node (ref "U$8") (pin "P$4") (pinfunction "DIN_P$4") (pintype "input"))
    )
    (net (code "18") (name "Net-(U$8-DOUT)") (class "Default")
      (node (ref "U$8") (pin "P$2") (pinfunction "DOUT_P$2") (pintype "output"))
      (node (ref "U$9") (pin "P$4") (pinfunction "DIN_P$4") (pintype "input"))
    )
    (net (code "19") (name "Net-(U$10-DIN)") (class "Default")
      (node (ref "U$10") (pin "P$4") (pinfunction "DIN_P$4") (pintype "input"))
      (node (ref "U$9") (pin "P$2") (pinfunction "DOUT_P$2") (pintype "output"))
    )
    (net (code "20") (name "Net-(U$11-DIN)") (class "Default")
      (node (ref "U$11") (pin "P$4") (pinfunction "DIN_P$4") (pintype "input"))
      (node (ref "U$30") (pin "P$2") (pinfunction "DOUT_P$2") (pintype "output"))
    )
    (net (code "21") (name "Net-(U$11-DOUT)") (class "Default")
      (node (ref "U$11") (pin "P$2") (pinfunction "DOUT_P$2") (pintype "output"))
      (node (ref "U$12") (pin "P$4") (pinfunction "DIN_P$4") (pintype "input"))
    )
    (net (code "22") (name "Net-(U$12-DOUT)") (class "Default")
      (node (ref "U$12") (pin "P$2") (pinfunction "DOUT_P$2") (pintype "output"))
      (node (ref "U$13") (pin "P$4") (pinfunction "DIN_P$4") (pintype "input"))
    )
    (net (code "23") (name "Net-(U$13-DOUT)") (class "Default")
      (node (ref "U$13") (pin "P$2") (pinfunction "DOUT_P$2") (pintype "output"))
      (node (ref "U$14") (pin "P$4") (pinfunction "DIN_P$4") (pintype "input"))
    )
    (net (code "24") (name "Net-(U$14-DOUT)") (class "Default")
      (node (ref "U$14") (pin "P$2") (pinfunction "DOUT_P$2") (pintype "output"))
      (node (ref "U$15") (pin "P$4") (pinfunction "DIN_P$4") (pintype "input"))
    )
    (net (code "25") (name "Net-(U$15-DOUT)") (class "Default")
      (node (ref "U$15") (pin "P$2") (pinfunction "DOUT_P$2") (pintype "output"))
      (node (ref "U$16") (pin "P$4") (pinfunction "DIN_P$4") (pintype "input"))
    )
    (net (code "26") (name "Net-(U$16-DOUT)") (class "Default")
      (node (ref "U$16") (pin "P$2") (pinfunction "DOUT_P$2") (pintype "output"))
      (node (ref "U$17") (pin "P$4") (pinfunction "DIN_P$4") (pintype "input"))
    )
    (net (code "27") (name "Net-(U$17-DOUT)") (class "Default")
      (node (ref "U$17") (pin "P$2") (pinfunction "DOUT_P$2") (pintype "output"))
      (node (ref "U$18") (pin "P$4") (pinfunction "DIN_P$4") (pintype "input"))
    )
    (net (code "28") (name "Net-(U$18-DOUT)") (class "Default")
      (node (ref "U$18") (pin "P$2") (pinfunction "DOUT_P$2") (pintype "output"))
      (node (ref "U$19") (pin "P$4") (pinfunction "DIN_P$4") (pintype "input"))
    )
    (net (code "29") (name "Net-(U$19-DOUT)") (class "Default")
      (node (ref "U$19") (pin "P$2") (pinfunction "DOUT_P$2") (pintype "output"))
      (node (ref "U$20") (pin "P$4") (pinfunction "DIN_P$4") (pintype "input"))
    )
    (net (code "30") (name "Net-(U$21-DIN)") (class "Default")
      (node (ref "U$21") (pin "P$4") (pinfunction "DIN_P$4") (pintype "input"))
      (node (ref "U$40") (pin "P$2") (pinfunction "DOUT_P$2") (pintype "output"))
    )
    (net (code "31") (name "Net-(U$21-DOUT)") (class "Default")
      (node (ref "U$21") (pin "P$2") (pinfunction "DOUT_P$2") (pintype "output"))
      (node (ref "U$22") (pin "P$4") (pinfunction "DIN_P$4") (pintype "input"))
    )
    (net (code "32") (name "Net-(U$22-DOUT)") (class "Default")
      (node (ref "U$22") (pin "P$2") (pinfunction "DOUT_P$2") (pintype "output"))
      (node (ref "U$23") (pin "P$4") (pinfunction "DIN_P$4") (pintype "input"))
    )
    (net (code "33") (name "Net-(U$23-DOUT)") (class "Default")
      (node (ref "U$23") (pin "P$2") (pinfunction "DOUT_P$2") (pintype "output"))
      (node (ref "U$24") (pin "P$4") (pinfunction "DIN_P$4") (pintype "input"))
    )
    (net (code "34") (name "Net-(U$24-DOUT)") (class "Default")
      (node (ref "U$24") (pin "P$2") (pinfunction "DOUT_P$2") (pintype "output"))
      (node (ref "U$25") (pin "P$4") (pinfunction "DIN_P$4") (pintype "input"))
    )
    (net (code "35") (name "Net-(U$25-DOUT)") (class "Default")
      (node (ref "U$25") (pin "P$2") (pinfunction "DOUT_P$2") (pintype "output"))
      (node (ref "U$26") (pin "P$4") (pinfunction "DIN_P$4") (pintype "input"))
    )
    (net (code "36") (name "Net-(U$26-DOUT)") (class "Default")
      (node (ref "U$26") (pin "P$2") (pinfunction "DOUT_P$2") (pintype "output"))
      (node (ref "U$27") (pin "P$4") (pinfunction "DIN_P$4") (pintype "input"))
    )
    (net (code "37") (name "Net-(U$27-DOUT)") (class "Default")
      (node (ref "U$27") (pin "P$2") (pinfunction "DOUT_P$2") (pintype "output"))
      (node (ref "U$28") (pin "P$4") (pinfunction "DIN_P$4") (pintype "input"))
    )
    (net (code "38") (name "Net-(U$28-DOUT)") (class "Default")
      (node (ref "U$28") (pin "P$2") (pinfunction "DOUT_P$2") (pintype "output"))
      (node (ref "U$29") (pin "P$4") (pinfunction "DIN_P$4") (pintype "input"))
    )
    (net (code "39") (name "Net-(U$29-DOUT)") (class "Default")
      (node (ref "U$29") (pin "P$2") (pinfunction "DOUT_P$2") (pintype "output"))
      (node (ref "U$30") (pin "P$4") (pinfunction "DIN_P$4") (pintype "input"))
    )
    (net (code "40") (name "Net-(U$31-DOUT)") (class "Default")
      (node (ref "U$31") (pin "P$2") (pinfunction "DOUT_P$2") (pintype "output"))
      (node (ref "U$32") (pin "P$4") (pinfunction "DIN_P$4") (pintype "input"))
    )
    (net (code "41") (name "Net-(U$32-DOUT)") (class "Default")
      (node (ref "U$32") (pin "P$2") (pinfunction "DOUT_P$2") (pintype "output"))
      (node (ref "U$33") (pin "P$4") (pinfunction "DIN_P$4") (pintype "input"))
    )
    (net (code "42") (name "Net-(U$33-DOUT)") (class "Default")
      (node (ref "U$33") (pin "P$2") (pinfunction "DOUT_P$2") (pintype "output"))
      (node (ref "U$34") (pin "P$4") (pinfunction "DIN_P$4") (pintype "input"))
    )
    (net (code "43") (name "Net-(U$34-DOUT)") (class "Default")
      (node (ref "U$34") (pin "P$2") (pinfunction "DOUT_P$2") (pintype "output"))
      (node (ref "U$35") (pin "P$4") (pinfunction "DIN_P$4") (pintype "input"))
    )
    (net (code "44") (name "Net-(U$35-DOUT)") (class "Default")
      (node (ref "U$35") (pin "P$2") (pinfunction "DOUT_P$2") (pintype "output"))
      (node (ref "U$36") (pin "P$4") (pinfunction "DIN_P$4") (pintype "input"))
    )
    (net (code "45") (name "Net-(U$36-DOUT)") (class "Default")
      (node (ref "U$36") (pin "P$2") (pinfunction "DOUT_P$2") (pintype "output"))
      (node (ref "U$37") (pin "P$4") (pinfunction "DIN_P$4") (pintype "input"))
    )
    (net (code "46") (name "Net-(U$37-DOUT)") (class "Default")
      (node (ref "U$37") (pin "P$2") (pinfunction "DOUT_P$2") (pintype "output"))
      (node (ref "U$38") (pin "P$4") (pinfunction "DIN_P$4") (pintype "input"))
    )
    (net (code "47") (name "Net-(U$38-DOUT)") (class "Default")
      (node (ref "U$38") (pin "P$2") (pinfunction "DOUT_P$2") (pintype "output"))
      (node (ref "U$39") (pin "P$4") (pinfunction "DIN_P$4") (pintype "input"))
    )
    (net (code "48") (name "Net-(U$39-DOUT)") (class "Default")
      (node (ref "U$39") (pin "P$2") (pinfunction "DOUT_P$2") (pintype "output"))
      (node (ref "U$40") (pin "P$4") (pinfunction "DIN_P$4") (pintype "input"))
    )
    (net (code "49") (name "Net-(U$41-DOUT)") (class "Default")
      (node (ref "U$41") (pin "P$2") (pinfunction "DOUT_P$2") (pintype "output"))
      (node (ref "U$42") (pin "P$4") (pinfunction "DIN_P$4") (pintype "input"))
    )
    (net (code "50") (name "Net-(U$42-DOUT)") (class "Default")
      (node (ref "U$42") (pin "P$2") (pinfunction "DOUT_P$2") (pintype "output"))
      (node (ref "U$43") (pin "P$4") (pinfunction "DIN_P$4") (pintype "input"))
    )
    (net (code "51") (name "Net-(U$43-DOUT)") (class "Default")
      (node (ref "U$43") (pin "P$2") (pinfunction "DOUT_P$2") (pintype "output"))
      (node (ref "U$44") (pin "P$4") (pinfunction "DIN_P$4") (pintype "input"))
    )
    (net (code "52") (name "Net-(U$44-DOUT)") (class "Default")
      (node (ref "U$44") (pin "P$2") (pinfunction "DOUT_P$2") (pintype "output"))
      (node (ref "U$45") (pin "P$4") (pinfunction "DIN_P$4") (pintype "input"))
    )
    (net (code "53") (name "Net-(U$45-DOUT)") (class "Default")
      (node (ref "U$45") (pin "P$2") (pinfunction "DOUT_P$2") (pintype "output"))
      (node (ref "U$46") (pin "P$4") (pinfunction "DIN_P$4") (pintype "input"))
    )
    (net (code "54") (name "Net-(U$46-DOUT)") (class "Default")
      (node (ref "U$46") (pin "P$2") (pinfunction "DOUT_P$2") (pintype "output"))
      (node (ref "U$47") (pin "P$4") (pinfunction "DIN_P$4") (pintype "input"))
    )
    (net (code "55") (name "Net-(U$47-DOUT)") (class "Default")
      (node (ref "U$47") (pin "P$2") (pinfunction "DOUT_P$2") (pintype "output"))
      (node (ref "U$48") (pin "P$4") (pinfunction "DIN_P$4") (pintype "input"))
    )
    (net (code "56") (name "Net-(U$48-DOUT)") (class "Default")
      (node (ref "U$48") (pin "P$2") (pinfunction "DOUT_P$2") (pintype "output"))
      (node (ref "U$49") (pin "P$4") (pinfunction "DIN_P$4") (pintype "input"))
    )
    (net (code "57") (name "Net-(U$49-DOUT)") (class "Default")
      (node (ref "U$49") (pin "P$2") (pinfunction "DOUT_P$2") (pintype "output"))
      (node (ref "U$50") (pin "P$4") (pinfunction "DIN_P$4") (pintype "input"))
    )
    (net (code "58") (name "Net-(U$50-DOUT)") (class "Default")
      (node (ref "U$50") (pin "P$2") (pinfunction "DOUT_P$2") (pintype "output"))
      (node (ref "U$51") (pin "P$4") (pinfunction "DIN_P$4") (pintype "input"))
    )
    (net (code "59") (name "Net-(U$51-DOUT)") (class "Default")
      (node (ref "U$51") (pin "P$2") (pinfunction "DOUT_P$2") (pintype "output"))
      (node (ref "U$52") (pin "P$4") (pinfunction "DIN_P$4") (pintype "input"))
    )
    (net (code "60") (name "Net-(U$52-DOUT)") (class "Default")
      (node (ref "U$52") (pin "P$2") (pinfunction "DOUT_P$2") (pintype "output"))
      (node (ref "U$53") (pin "P$4") (pinfunction "DIN_P$4") (pintype "input"))
    )
    (net (code "61") (name "Net-(U$53-DOUT)") (class "Default")
      (node (ref "U$53") (pin "P$2") (pinfunction "DOUT_P$2") (pintype "output"))
      (node (ref "U$54") (pin "P$4") (pinfunction "DIN_P$4") (pintype "input"))
    )
    (net (code "62") (name "Net-(U$54-DOUT)") (class "Default")
      (node (ref "U$54") (pin "P$2") (pinfunction "DOUT_P$2") (pintype "output"))
      (node (ref "U$55") (pin "P$4") (pinfunction "DIN_P$4") (pintype "input"))
    )
    (net (code "63") (name "Net-(U$55-DOUT)") (class "Default")
      (node (ref "U$55") (pin "P$2") (pinfunction "DOUT_P$2") (pintype "output"))
      (node (ref "U$56") (pin "P$4") (pinfunction "DIN_P$4") (pintype "input"))
    )
    (net (code "64") (name "Net-(U$56-DOUT)") (class "Default")
      (node (ref "U$56") (pin "P$2") (pinfunction "DOUT_P$2") (pintype "output"))
      (node (ref "U$57") (pin "P$4") (pinfunction "DIN_P$4") (pintype "input"))
    )
    (net (code "65") (name "Net-(U1-PB3)") (class "Default")
      (node (ref "C64") (pin "1") (pinfunction "1_1") (pintype "passive"))
      (node (ref "Q1") (pin "1") (pinfunction "1_1") (pintype "passive"))
      (node (ref "U1") (pin "2") (pinfunction "PB3_2") (pintype "bidirectional"))
    )
    (net (code "66") (name "Net-(U1-PB4)") (class "Default")
      (node (ref "C63") (pin "2") (pinfunction "2_2") (pintype "passive"))
      (node (ref "Q1") (pin "2") (pinfunction "2_2") (pintype "passive"))
      (node (ref "U1") (pin "3") (pinfunction "PB4_3") (pintype "bidirectional"))
    )
  )
)
